# IMU.net
KiCad netlist of a schematic drawn in Altium Designer
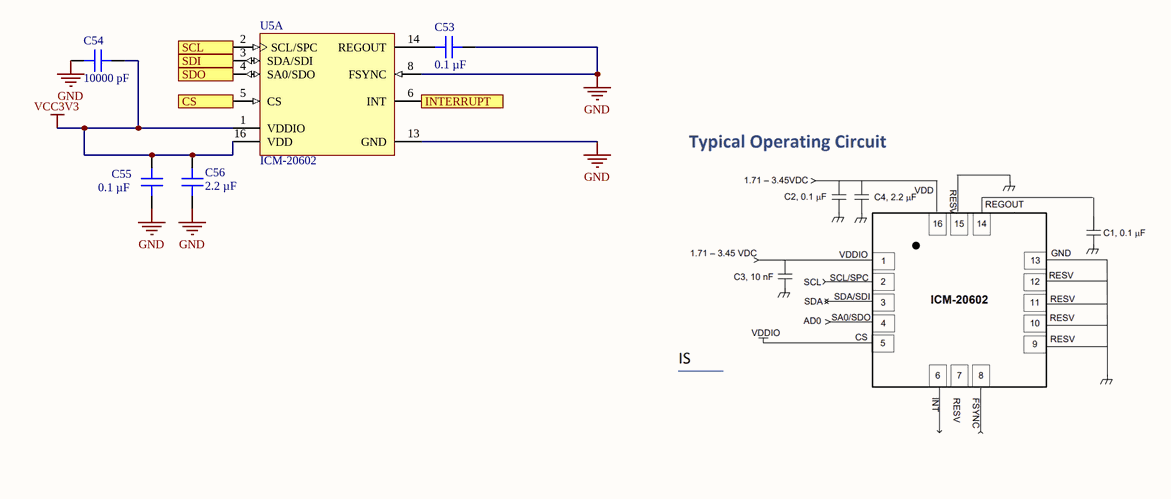
[diagram p0: IMU.SchDoc]

(export (version "E")
  (design (tool "Eeschema 10.0.6"))
  (components
    (comp (ref "C53")
      (value "0.1 µF")
      (footprint "CAP 0603_1608")
      (description "CAP CER 0.1UF 50V X7R 0603")
      (fields (field (name "PART NUMBER") "C0603C104K5RAC7411") (field (name "MANUFACTURER") "KEMET"))
      (libsource (lib "Celestial Altium Library - altium_library") (part "Capacitor"))
    )
    (comp (ref "C54")
      (value "10000 pF")
      (footprint "CAP 0603_1608")
      (description "CAP CER 0603 10NF 16V X7R 10%")
      (fields (field (name "PART NUMBER") "C0603C103K4RECAUTO") (field (name "MANUFACTURER") "KEMET"))
      (libsource (lib "Celestial Altium Library - altium_library") (part "Capacitor"))
    )
    (comp (ref "C55")
      (value "0.1 µF")
      (footprint "CAP 0603_1608")
      (description "CAP CER 0.1UF 50V X7R 0603")
      (fields (field (name "PART NUMBER") "C0603C104K5RAC7411") (field (name "MANUFACTURER") "KEMET"))
      (libsource (lib "Celestial Altium Library - altium_library") (part "Capacitor"))
    )
    (comp (ref "C56")
      (value "2.2 µF")
      (footprint "CAP 0603_1608")
      (description "CAP CER 2.2UF 10V Y5V 0603")
      (fields (field (name "PART NUMBER") "CC0603ZRY5V6BB225") (field (name "MANUFACTURER") "Yageo"))
      (libsource (lib "Celestial Altium Library - altium_library") (part "Capacitor"))
    )
    (comp (ref "U5")
      (value "ICM-20602")
      (footprint "INSE-I62-16")
      (fields (field (name "MANUFACTURER") "InvenSense"))
      (libsource (lib "Altium Content Vault") (part "INSE-ICM-20602-16"))
    )
  )
  (nets
    (net (code "1") (name "/CS") (class "Default")
      (node (ref "U5") (pin "5") (pinfunction "CS_5") (pintype "input"))
    )
    (net (code "2") (name "/INTERRUPT") (class "Default")
      (node (ref "U5") (pin "6") (pinfunction "INT_6") (pintype "open_collector"))
    )
    (net (code "3") (name "/SCL") (class "Default")
      (node (ref "U5") (pin "2") (pinfunction "SCL/SPC_2") (pintype "input"))
    )
    (net (code "4") (name "/SDI") (class "Default")
      (node (ref "U5") (pin "3") (pinfunction "SDA/SDI_3") (pintype "bidirectional"))
    )
    (net (code "5") (name "/SDO") (class "Default")
      (node (ref "U5") (pin "4") (pinfunction "SA0/SDO_4") (pintype "bidirectional"))
    )
    (net (code "6") (name "GND") (class "Default")
      (node (ref "C53") (pin "2") (pinfunction "2_2") (pintype "passive"))
      (node (ref "C54") (pin "1") (pinfunction "1_1") (pintype "passive"))
      (node (ref "C55") (pin "1") (pinfunction "1_1") (pintype "passive"))
      (node (ref "C56") (pin "1") (pinfunction "1_1") (pintype "passive"))
      (node (ref "U5") (pin "13") (pinfunction "GND_13") (pintype "power_in"))
      (node (ref "U5") (pin "8") (pinfunction "FSYNC_8") (pintype "input"))
    )
    (net (code "7") (name "Net-(U5A-REGOUT)") (class "Default")
      (node (ref "C53") (pin "1") (pinfunction "1_1") (pintype "passive"))
      (node (ref "U5") (pin "14") (pinfunction "REGOUT_14") (pintype "passive"))
    )
    (net (code "8") (name "VCC3V3") (class "Default")
      (node (ref "C54") (pin "2") (pinfunction "2_2") (pintype "passive"))
      (node (ref "C55") (pin "2") (pinfunction "2_2") (pintype "passive"))
      (node (ref "C56") (pin "2") (pinfunction "2_2") (pintype "passive"))
      (node (ref "U5") (pin "1") (pinfunction "VDDIO_1") (pintype "power_in"))
      (node (ref "U5") (pin "16") (pinfunction "VDD_16") (pintype "power_in"))
    )
  )
)
